# DACEM_Final_Bckup.net
KiCad netlist of a schematic drawn in EAGLE
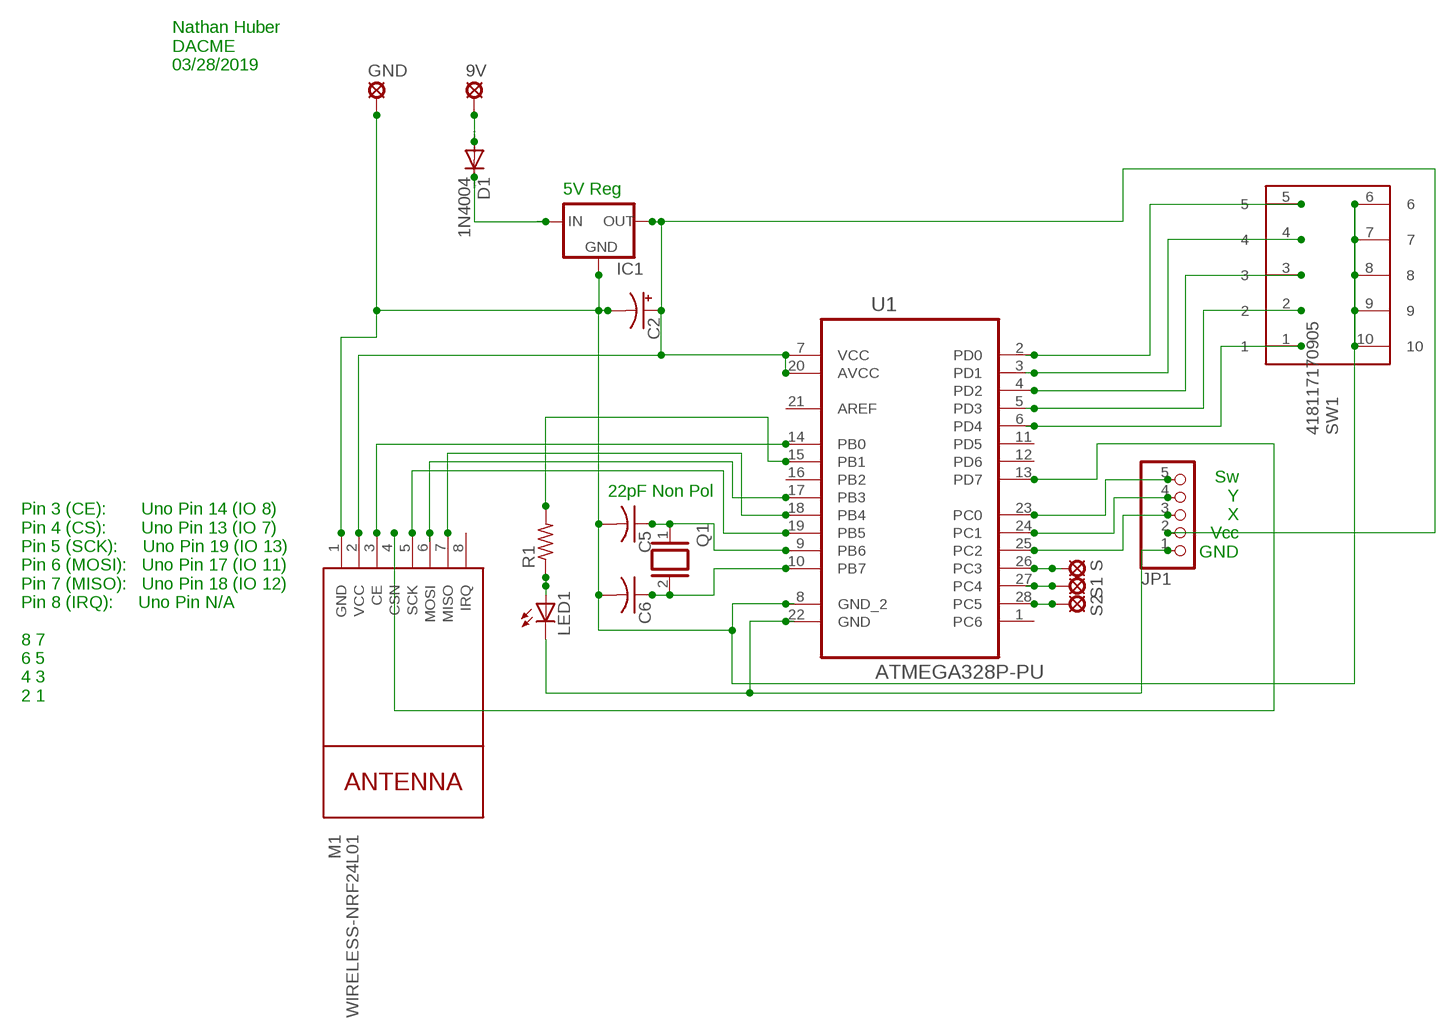
[diagram p0: schematic, sheet 1]

(export (version "E")
  (design (tool "Eeschema 10.0.6"))
  (components
    (comp (ref "9V")
      (value "LSP10")
      (footprint "eagle-import:LSP10")
      (libsource (lib "eagle-import") (part "LSP10"))
    )
    (comp (ref "C2")
      (value "CPOL-USE1.8-4")
      (footprint "eagle-import:E1,8-4")
      (libsource (lib "eagle-import") (part "CPOL-USE1.8-4"))
    )
    (comp (ref "C5")
      (value "C-US025-025X050")
      (footprint "eagle-import:C025-025X050")
      (libsource (lib "eagle-import") (part "C-US025-025X050"))
    )
    (comp (ref "C6")
      (value "C-US025-025X050")
      (footprint "eagle-import:C025-025X050")
      (libsource (lib "eagle-import") (part "C-US025-025X050"))
    )
    (comp (ref "D1")
      (value "1N4004")
      (footprint "eagle-import:DO41-10")
      (libsource (lib "eagle-import") (part "1N4004"))
    )
    (comp (ref "GND")
      (value "LSP10")
      (footprint "eagle-import:LSP10")
      (libsource (lib "eagle-import") (part "LSP10"))
    )
    (comp (ref "IC1")
      (value "78XXS")
      (footprint "eagle-import:78XXS")
      (libsource (lib "eagle-import") (part "78XXS"))
    )
    (comp (ref "JP1")
      (value "PINHD-1X5")
      (footprint "eagle-import:1X05")
      (libsource (lib "eagle-import") (part "PINHD-1X5"))
    )
    (comp (ref "LED1")
      (value "LED3MM")
      (footprint "eagle-import:LED3MM")
      (libsource (lib "eagle-import") (part "LED3MM"))
    )
    (comp (ref "M1")
      (value "WIRELESS-NRF24L01")
      (footprint "eagle-import:WIRELESS-NRF24L01")
      (libsource (lib "eagle-import") (part "WIRELESS-NRF24L01"))
    )
    (comp (ref "Q1")
      (value "XTAL")
      (footprint "eagle-import:Q")
      (libsource (lib "eagle-import") (part "XTAL"))
    )
    (comp (ref "R1")
      (value "R-US_0207/12")
      (footprint "eagle-import:0207_12")
      (libsource (lib "eagle-import") (part "R-US_0207/12"))
    )
    (comp (ref "S")
      (value "LSP10")
      (footprint "eagle-import:LSP10")
      (libsource (lib "eagle-import") (part "LSP10"))
    )
    (comp (ref "S1")
      (value "LSP10")
      (footprint "eagle-import:LSP10")
      (libsource (lib "eagle-import") (part "LSP10"))
    )
    (comp (ref "S2")
      (value "LSP10")
      (footprint "eagle-import:LSP10")
      (libsource (lib "eagle-import") (part "LSP10"))
    )
    (comp (ref "SW1")
      (value "418117170905")
      (footprint "eagle-import:418117170905")
      (libsource (lib "eagle-import") (part "418117170905"))
    )
    (comp (ref "U1")
      (value "ATMEGA328P-PU")
      (footprint "eagle-import:DIP254P762X457-28")
      (libsource (lib "eagle-import") (part "ATMEGA328P-PU"))
    )
  )
  (nets
    (net (code "1") (name "Net-(9V-PadMP)") (class "Default")
      (node (ref "9V") (pin "MP") (pinfunction "MP_MP") (pintype "passive"))
      (node (ref "D1") (pin "A") (pinfunction "A_A") (pintype "passive"))
    )
    (net (code "2") (name "Net-(D1-PadC)") (class "Default")
      (node (ref "D1") (pin "C") (pinfunction "C_C") (pintype "passive"))
      (node (ref "IC1") (pin "IN") (pinfunction "IN_IN") (pintype "input"))
    )
    (net (code "3") (name "Net-(LED1-C)") (class "Default")
      (node (ref "JP1") (pin "1") (pinfunction "1_1") (pintype "passive"))
      (node (ref "LED1") (pin "K") (pinfunction "C_K") (pintype "passive"))
      (node (ref "U1") (pin "22") (pinfunction "GND_22") (pintype "passive"))
    )
    (net (code "4") (name "Net-(LED1-PadA)") (class "Default")
      (node (ref "LED1") (pin "A") (pinfunction "A_A") (pintype "passive"))
      (node (ref "R1") (pin "1") (pinfunction "1_1") (pintype "passive"))
    )
    (net (code "5") (name "Net-(M1-CE)") (class "Default")
      (node (ref "M1") (pin "3") (pinfunction "CE_3") (pintype "bidirectional"))
      (node (ref "U1") (pin "14") (pinfunction "PB0_14") (pintype "bidirectional"))
    )
    (net (code "6") (name "Net-(M1-CSN)") (class "Default")
      (node (ref "M1") (pin "4") (pinfunction "CSN_4") (pintype "bidirectional"))
      (node (ref "U1") (pin "13") (pinfunction "PD7_13") (pintype "bidirectional"))
    )
    (net (code "7") (name "Net-(M1-GND)") (class "Default")
      (node (ref "C2") (pin "-") (pinfunction "-_-") (pintype "passive"))
      (node (ref "C5") (pin "2") (pinfunction "2_2") (pintype "passive"))
      (node (ref "C6") (pin "2") (pinfunction "2_2") (pintype "passive"))
      (node (ref "GND") (pin "MP") (pinfunction "MP_MP") (pintype "passive"))
      (node (ref "IC1") (pin "GND") (pinfunction "GND_GND") (pintype "input"))
      (node (ref "M1") (pin "1") (pinfunction "GND_1") (pintype "power_in"))
      (node (ref "SW1") (pin "10") (pinfunction "10_10") (pintype "bidirectional"))
      (node (ref "SW1") (pin "6") (pinfunction "6_6") (pintype "bidirectional"))
      (node (ref "SW1") (pin "7") (pinfunction "7_7") (pintype "bidirectional"))
      (node (ref "SW1") (pin "8") (pinfunction "8_8") (pintype "bidirectional"))
      (node (ref "SW1") (pin "9") (pinfunction "9_9") (pintype "bidirectional"))
      (node (ref "U1") (pin "8") (pinfunction "GND_2_8") (pintype "passive"))
    )
    (net (code "8") (name "Net-(M1-MISO)") (class "Default")
      (node (ref "M1") (pin "7") (pinfunction "MISO_7") (pintype "bidirectional"))
      (node (ref "U1") (pin "18") (pinfunction "PB4_18") (pintype "bidirectional"))
    )
    (net (code "9") (name "Net-(M1-MOSI)") (class "Default")
      (node (ref "M1") (pin "6") (pinfunction "MOSI_6") (pintype "bidirectional"))
      (node (ref "U1") (pin "17") (pinfunction "PB3_17") (pintype "bidirectional"))
    )
    (net (code "10") (name "Net-(M1-SCK)") (class "Default")
      (node (ref "M1") (pin "5") (pinfunction "SCK_5") (pintype "bidirectional"))
      (node (ref "U1") (pin "19") (pinfunction "PB5_19") (pintype "bidirectional"))
    )
    (net (code "11") (name "Net-(M1-VCC)") (class "Default")
      (node (ref "C2") (pin "+") (pinfunction "+_+") (pintype "passive"))
      (node (ref "IC1") (pin "OUT") (pinfunction "OUT_OUT") (pintype "passive"))
      (node (ref "JP1") (pin "2") (pinfunction "2_2") (pintype "passive"))
      (node (ref "M1") (pin "2") (pinfunction "VCC_2") (pintype "power_in"))
      (node (ref "U1") (pin "20") (pinfunction "AVCC_20") (pintype "power_in"))
      (node (ref "U1") (pin "7") (pinfunction "VCC_7") (pintype "power_in"))
    )
    (net (code "12") (name "Net-(U1-PB1)") (class "Default")
      (node (ref "R1") (pin "2") (pinfunction "2_2") (pintype "passive"))
      (node (ref "U1") (pin "15") (pinfunction "PB1_15") (pintype "bidirectional"))
    )
    (net (code "13") (name "Net-(U1-PB6)") (class "Default")
      (node (ref "C5") (pin "1") (pinfunction "1_1") (pintype "passive"))
      (node (ref "Q1") (pin "1") (pinfunction "1_1") (pintype "passive"))
      (node (ref "U1") (pin "9") (pinfunction "PB6_9") (pintype "bidirectional"))
    )
    (net (code "14") (name "Net-(U1-PB7)") (class "Default")
      (node (ref "C6") (pin "1") (pinfunction "1_1") (pintype "passive"))
      (node (ref "Q1") (pin "2") (pinfunction "2_2") (pintype "passive"))
      (node (ref "U1") (pin "10") (pinfunction "PB7_10") (pintype "bidirectional"))
    )
    (net (code "15") (name "Net-(U1-PC0)") (class "Default")
      (node (ref "JP1") (pin "5") (pinfunction "5_5") (pintype "passive"))
      (node (ref "U1") (pin "23") (pinfunction "PC0_23") (pintype "bidirectional"))
    )
    (net (code "16") (name "Net-(U1-PC1)") (class "Default")
      (node (ref "JP1") (pin "4") (pinfunction "4_4") (pintype "passive"))
      (node (ref "U1") (pin "24") (pinfunction "PC1_24") (pintype "bidirectional"))
    )
    (net (code "17") (name "Net-(U1-PC2)") (class "Default")
      (node (ref "JP1") (pin "3") (pinfunction "3_3") (pintype "passive"))
      (node (ref "U1") (pin "25") (pinfunction "PC2_25") (pintype "bidirectional"))
    )
    (net (code "18") (name "Net-(U1-PC3)") (class "Default")
      (node (ref "S") (pin "MP") (pinfunction "MP_MP") (pintype "passive"))
      (node (ref "U1") (pin "26") (pinfunction "PC3_26") (pintype "bidirectional"))
    )
    (net (code "19") (name "Net-(U1-PC4)") (class "Default")
      (node (ref "S1") (pin "MP") (pinfunction "MP_MP") (pintype "passive"))
      (node (ref "U1") (pin "27") (pinfunction "PC4_27") (pintype "bidirectional"))
    )
    (net (code "20") (name "Net-(U1-PC5)") (class "Default")
      (node (ref "S2") (pin "MP") (pinfunction "MP_MP") (pintype "passive"))
      (node (ref "U1") (pin "28") (pinfunction "PC5_28") (pintype "bidirectional"))
    )
    (net (code "21") (name "Net-(U1-PD0)") (class "Default")
      (node (ref "SW1") (pin "5") (pinfunction "5_5") (pintype "bidirectional"))
      (node (ref "U1") (pin "2") (pinfunction "PD0_2") (pintype "bidirectional"))
    )
    (net (code "22") (name "Net-(U1-PD1)") (class "Default")
      (node (ref "SW1") (pin "4") (pinfunction "4_4") (pintype "bidirectional"))
      (node (ref "U1") (pin "3") (pinfunction "PD1_3") (pintype "bidirectional"))
    )
    (net (code "23") (name "Net-(U1-PD2)") (class "Default")
      (node (ref "SW1") (pin "3") (pinfunction "3_3") (pintype "bidirectional"))
      (node (ref "U1") (pin "4") (pinfunction "PD2_4") (pintype "bidirectional"))
    )
    (net (code "24") (name "Net-(U1-PD3)") (class "Default")
      (node (ref "SW1") (pin "2") (pinfunction "2_2") (pintype "bidirectional"))
      (node (ref "U1") (pin "5") (pinfunction "PD3_5") (pintype "bidirectional"))
    )
    (net (code "25") (name "Net-(U1-PD4)") (class "Default")
      (node (ref "SW1") (pin "1") (pinfunction "1_1") (pintype "bidirectional"))
      (node (ref "U1") (pin "6") (pinfunction "PD4_6") (pintype "bidirectional"))
    )
    (net (code "26") (name "unconnected-(M1-IRQ-Pad8)") (class "Default")
      (node (ref "M1") (pin "8") (pinfunction "IRQ_8") (pintype "bidirectional"))
    )
    (net (code "27") (name "unconnected-(U1-AREF-Pad21)") (class "Default")
      (node (ref "U1") (pin "21") (pinfunction "AREF_21") (pintype "input"))
    )
    (net (code "28") (name "unconnected-(U1-PB2-Pad16)") (class "Default")
      (node (ref "U1") (pin "16") (pinfunction "PB2_16") (pintype "bidirectional"))
    )
    (net (code "29") (name "unconnected-(U1-PC6-Pad1)") (class "Default")
      (node (ref "U1") (pin "1") (pinfunction "PC6_1") (pintype "bidirectional"))
    )
    (net (code "30") (name "unconnected-(U1-PD5-Pad11)") (class "Default")
      (node (ref "U1") (pin "11") (pinfunction "PD5_11") (pintype "bidirectional"))
    )
    (net (code "31") (name "unconnected-(U1-PD6-Pad12)") (class "Default")
      (node (ref "U1") (pin "12") (pinfunction "PD6_12") (pintype "bidirectional"))
    )
  )
)
